# 98_Power_Test.net
KiCad netlist of a schematic drawn in Altium Designer
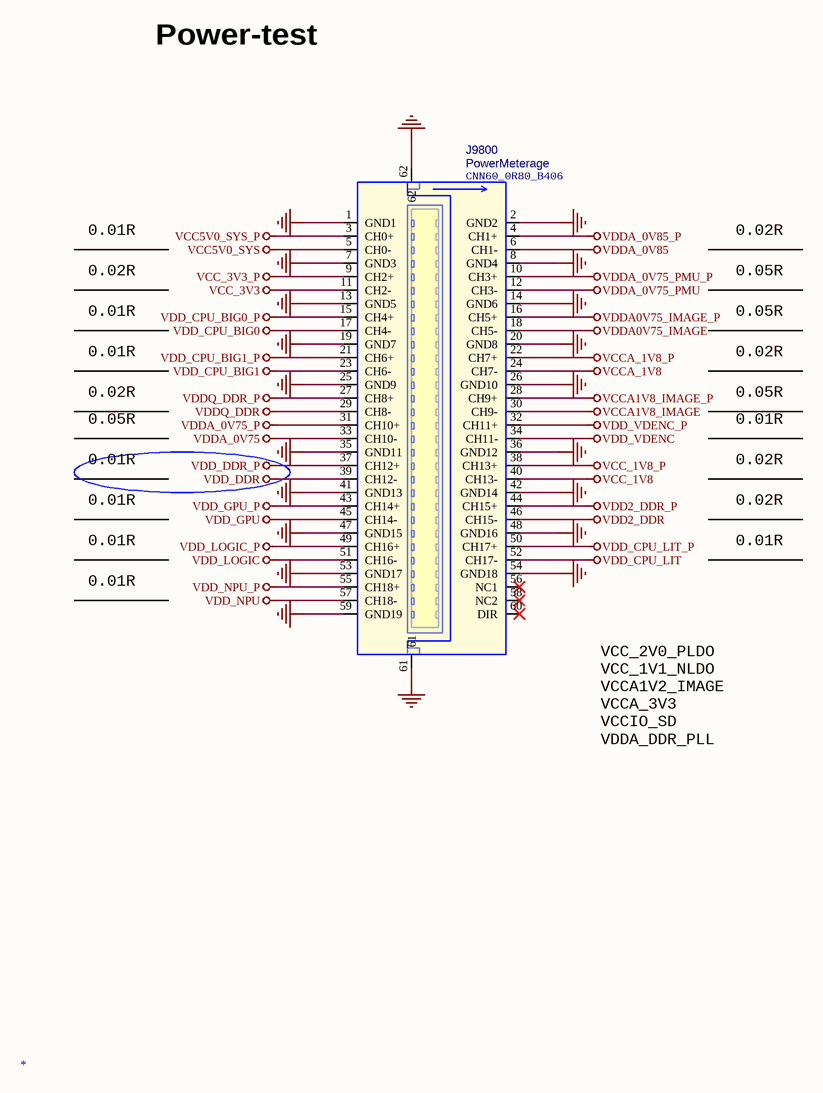
[diagram p0: 98.Power Test.SchDoc]

(export (version "E")
  (design (tool "Eeschema 10.0.6"))
  (components
    (comp (ref "J9800")
      (value "*")
      (footprint "CNN60_0R80_B406")
      (fields
        (field (name "PCB FOOTPRINT") "CNN60_0R80_B406")
        (field (name "ALTIUM_UNNAMED_1") "PowerMeterage")
      )
      (libsource (lib "*") (part "PowerMeasurement_6"))
    )
  )
  (nets
    (net (code "1") (name "GND") (class "Default")
      (node (ref "J9800") (pin "1") (pinfunction "GND1_1") (pintype "passive"))
      (node (ref "J9800") (pin "13") (pinfunction "GND5_13") (pintype "passive"))
      (node (ref "J9800") (pin "14") (pinfunction "GND6_14") (pintype "passive"))
      (node (ref "J9800") (pin "19") (pinfunction "GND7_19") (pintype "passive"))
      (node (ref "J9800") (pin "2") (pinfunction "GND2_2") (pintype "passive"))
      (node (ref "J9800") (pin "20") (pinfunction "GND8_20") (pintype "passive"))
      (node (ref "J9800") (pin "25") (pinfunction "GND9_25") (pintype "passive"))
      (node (ref "J9800") (pin "26") (pinfunction "GND10_26") (pintype "passive"))
      (node (ref "J9800") (pin "35") (pinfunction "GND11_35") (pintype "passive"))
      (node (ref "J9800") (pin "36") (pinfunction "GND12_36") (pintype "passive"))
      (node (ref "J9800") (pin "41") (pinfunction "GND13_41") (pintype "passive"))
      (node (ref "J9800") (pin "42") (pinfunction "GND14_42") (pintype "passive"))
      (node (ref "J9800") (pin "47") (pinfunction "GND15_47") (pintype "passive"))
      (node (ref "J9800") (pin "48") (pinfunction "GND16_48") (pintype "passive"))
      (node (ref "J9800") (pin "53") (pinfunction "GND17_53") (pintype "passive"))
      (node (ref "J9800") (pin "54") (pinfunction "GND18_54") (pintype "passive"))
      (node (ref "J9800") (pin "59") (pinfunction "GND19_59") (pintype "passive"))
      (node (ref "J9800") (pin "61") (pinfunction "61_61") (pintype "passive"))
      (node (ref "J9800") (pin "62") (pinfunction "62_62") (pintype "passive"))
      (node (ref "J9800") (pin "7") (pinfunction "GND3_7") (pintype "passive"))
      (node (ref "J9800") (pin "8") (pinfunction "GND4_8") (pintype "passive"))
    )
    (net (code "2") (name "VCC5V0_SYS") (class "Default")
      (node (ref "J9800") (pin "5") (pinfunction "CH0-_5") (pintype "passive"))
    )
    (net (code "3") (name "VCC5V0_SYS_P") (class "Default")
      (node (ref "J9800") (pin "3") (pinfunction "CH0+_3") (pintype "passive"))
    )
    (net (code "4") (name "VCCA1V8_IMAGE") (class "Default")
      (node (ref "J9800") (pin "30") (pinfunction "CH9-_30") (pintype "passive"))
    )
    (net (code "5") (name "VCCA1V8_IMAGE_P") (class "Default")
      (node (ref "J9800") (pin "28") (pinfunction "CH9+_28") (pintype "passive"))
    )
    (net (code "6") (name "VCCA_1V8") (class "Default")
      (node (ref "J9800") (pin "24") (pinfunction "CH7-_24") (pintype "passive"))
    )
    (net (code "7") (name "VCCA_1V8_P") (class "Default")
      (node (ref "J9800") (pin "22") (pinfunction "CH7+_22") (pintype "passive"))
    )
    (net (code "8") (name "VCC_1V8") (class "Default")
      (node (ref "J9800") (pin "40") (pinfunction "CH13-_40") (pintype "passive"))
    )
    (net (code "9") (name "VCC_1V8_P") (class "Default")
      (node (ref "J9800") (pin "38") (pinfunction "CH13+_38") (pintype "passive"))
    )
    (net (code "10") (name "VCC_3V3") (class "Default")
      (node (ref "J9800") (pin "11") (pinfunction "CH2-_11") (pintype "passive"))
    )
    (net (code "11") (name "VCC_3V3_P") (class "Default")
      (node (ref "J9800") (pin "9") (pinfunction "CH2+_9") (pintype "passive"))
    )
    (net (code "12") (name "VDD2_DDR") (class "Default")
      (node (ref "J9800") (pin "46") (pinfunction "CH15-_46") (pintype "passive"))
    )
    (net (code "13") (name "VDD2_DDR_P") (class "Default")
      (node (ref "J9800") (pin "44") (pinfunction "CH15+_44") (pintype "passive"))
    )
    (net (code "14") (name "VDDA0V75_IMAGE") (class "Default")
      (node (ref "J9800") (pin "18") (pinfunction "CH5-_18") (pintype "passive"))
    )
    (net (code "15") (name "VDDA0V75_IMAGE_P") (class "Default")
      (node (ref "J9800") (pin "16") (pinfunction "CH5+_16") (pintype "passive"))
    )
    (net (code "16") (name "VDDA_0V75") (class "Default")
      (node (ref "J9800") (pin "33") (pinfunction "CH10-_33") (pintype "passive"))
    )
    (net (code "17") (name "VDDA_0V75_P") (class "Default")
      (node (ref "J9800") (pin "31") (pinfunction "CH10+_31") (pintype "passive"))
    )
    (net (code "18") (name "VDDA_0V75_PMU") (class "Default")
      (node (ref "J9800") (pin "12") (pinfunction "CH3-_12") (pintype "passive"))
    )
    (net (code "19") (name "VDDA_0V75_PMU_P") (class "Default")
      (node (ref "J9800") (pin "10") (pinfunction "CH3+_10") (pintype "passive"))
    )
    (net (code "20") (name "VDDA_0V85") (class "Default")
      (node (ref "J9800") (pin "6") (pinfunction "CH1-_6") (pintype "passive"))
    )
    (net (code "21") (name "VDDA_0V85_P") (class "Default")
      (node (ref "J9800") (pin "4") (pinfunction "CH1+_4") (pintype "passive"))
    )
    (net (code "22") (name "VDDQ_DDR") (class "Default")
      (node (ref "J9800") (pin "29") (pinfunction "CH8-_29") (pintype "passive"))
    )
    (net (code "23") (name "VDDQ_DDR_P") (class "Default")
      (node (ref "J9800") (pin "27") (pinfunction "CH8+_27") (pintype "passive"))
    )
    (net (code "24") (name "VDD_CPU_BIG0") (class "Default")
      (node (ref "J9800") (pin "17") (pinfunction "CH4-_17") (pintype "passive"))
    )
    (net (code "25") (name "VDD_CPU_BIG0_P") (class "Default")
      (node (ref "J9800") (pin "15") (pinfunction "CH4+_15") (pintype "passive"))
    )
    (net (code "26") (name "VDD_CPU_BIG1") (class "Default")
      (node (ref "J9800") (pin "23") (pinfunction "CH6-_23") (pintype "passive"))
    )
    (net (code "27") (name "VDD_CPU_BIG1_P") (class "Default")
      (node (ref "J9800") (pin "21") (pinfunction "CH6+_21") (pintype "passive"))
    )
    (net (code "28") (name "VDD_CPU_LIT") (class "Default")
      (node (ref "J9800") (pin "52") (pinfunction "CH17-_52") (pintype "passive"))
    )
    (net (code "29") (name "VDD_CPU_LIT_P") (class "Default")
      (node (ref "J9800") (pin "50") (pinfunction "CH17+_50") (pintype "passive"))
    )
    (net (code "30") (name "VDD_DDR") (class "Default")
      (node (ref "J9800") (pin "39") (pinfunction "CH12-_39") (pintype "passive"))
    )
    (net (code "31") (name "VDD_DDR_P") (class "Default")
      (node (ref "J9800") (pin "37") (pinfunction "CH12+_37") (pintype "passive"))
    )
    (net (code "32") (name "VDD_GPU") (class "Default")
      (node (ref "J9800") (pin "45") (pinfunction "CH14-_45") (pintype "passive"))
    )
    (net (code "33") (name "VDD_GPU_P") (class "Default")
      (node (ref "J9800") (pin "43") (pinfunction "CH14+_43") (pintype "passive"))
    )
    (net (code "34") (name "VDD_LOGIC") (class "Default")
      (node (ref "J9800") (pin "51") (pinfunction "CH16-_51") (pintype "passive"))
    )
    (net (code "35") (name "VDD_LOGIC_P") (class "Default")
      (node (ref "J9800") (pin "49") (pinfunction "CH16+_49") (pintype "passive"))
    )
    (net (code "36") (name "VDD_NPU") (class "Default")
      (node (ref "J9800") (pin "57") (pinfunction "CH18-_57") (pintype "passive"))
    )
    (net (code "37") (name "VDD_NPU_P") (class "Default")
      (node (ref "J9800") (pin "55") (pinfunction "CH18+_55") (pintype "passive"))
    )
    (net (code "38") (name "VDD_VDENC") (class "Default")
      (node (ref "J9800") (pin "34") (pinfunction "CH11-_34") (pintype "passive"))
    )
    (net (code "39") (name "VDD_VDENC_P") (class "Default")
      (node (ref "J9800") (pin "32") (pinfunction "CH11+_32") (pintype "passive"))
    )
    (net (code "40") (name "unconnected-(J9800-DIR-Pad60)") (class "Default")
      (node (ref "J9800") (pin "60") (pinfunction "DIR_60") (pintype "passive+no_connect"))
    )
    (net (code "41") (name "unconnected-(J9800-NC1-Pad56)") (class "Default")
      (node (ref "J9800") (pin "56") (pinfunction "NC1_56") (pintype "passive+no_connect"))
    )
    (net (code "42") (name "unconnected-(J9800-NC2-Pad58)") (class "Default")
      (node (ref "J9800") (pin "58") (pinfunction "NC2_58") (pintype "passive+no_connect"))
    )
  )
)
